# EVmulator_T85.net
KiCad netlist of a schematic drawn in EAGLE
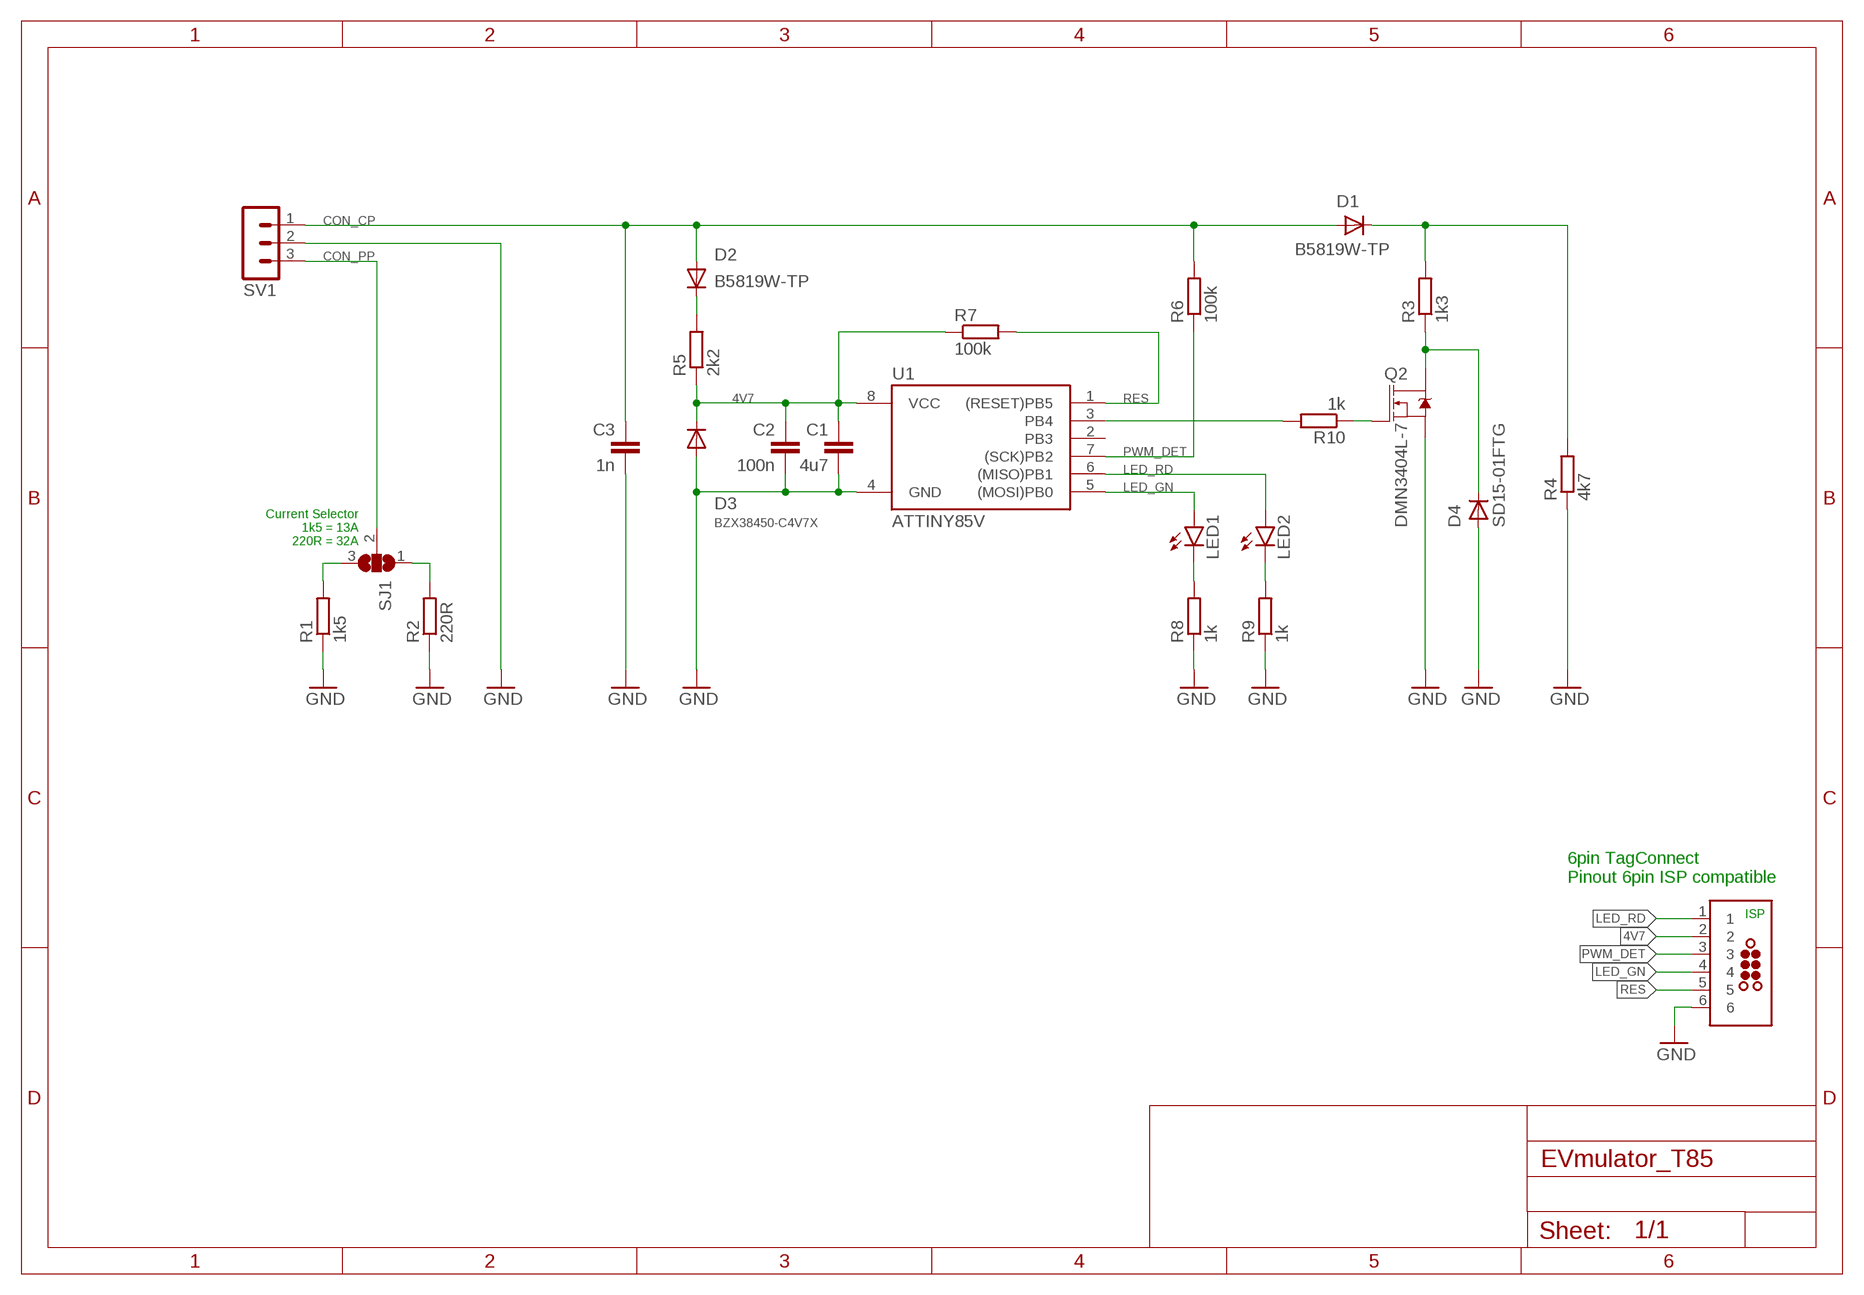
[diagram p0: schematic, sheet 1]

(export (version "E")
  (design (tool "Eeschema 10.0.6"))
  (components
    (comp (ref "C1")
      (value "4u7")
      (footprint "eagle-import:C0603")
      (libsource (lib "eagle-import") (part "C-EUC0603"))
    )
    (comp (ref "C2")
      (value "100n")
      (footprint "eagle-import:C0603")
      (libsource (lib "eagle-import") (part "C-EUC0603"))
    )
    (comp (ref "C3")
      (value "1n")
      (footprint "eagle-import:C0603")
      (libsource (lib "eagle-import") (part "C-EUC0603"))
    )
    (comp (ref "D1")
      (value "B5819W-TP")
      (footprint "eagle-import:SOD-123")
      (libsource (lib "eagle-import") (part "DIODESOD-123"))
    )
    (comp (ref "D2")
      (value "B5819W-TP")
      (footprint "eagle-import:SOD-123")
      (libsource (lib "eagle-import") (part "DIODESOD-123"))
    )
    (comp (ref "D3")
      (value "BZX38450-C4V7X")
      (footprint "eagle-import:SOD-323F")
      (libsource (lib "eagle-import") (part "DIODESOD-323F"))
    )
    (comp (ref "D4")
      (value "SD15-01FTG")
      (footprint "eagle-import:SOD-323F")
      (libsource (lib "eagle-import") (part "DIODESOD-323F"))
    )
    (comp (ref "J1")
      (value "TAG-CONNECT_TC2030-MCP-NL")
      (footprint "eagle-import:TAG-CONNECT_TC2030-MCP-NL")
      (libsource (lib "eagle-import") (part "TAG-CONNECT_TC2030-MCP-NL"))
    )
    (comp (ref "LED1")
      (value "LEDCHIP-LED0603")
      (footprint "eagle-import:CHIP-LED0603")
      (libsource (lib "eagle-import") (part "LEDCHIP-LED0603"))
    )
    (comp (ref "LED2")
      (value "LEDCHIP-LED0603")
      (footprint "eagle-import:CHIP-LED0603")
      (libsource (lib "eagle-import") (part "LEDCHIP-LED0603"))
    )
    (comp (ref "Q2")
      (value "DMN3404L-7")
      (footprint "eagle-import:SOT23-3")
      (libsource (lib "eagle-import") (part "MOSFET-NCH-AO3404A"))
    )
    (comp (ref "R1")
      (value "1k5")
      (footprint "eagle-import:R0805")
      (libsource (lib "eagle-import") (part "R-EU_R0805"))
    )
    (comp (ref "R2")
      (value "220R")
      (footprint "eagle-import:R0805")
      (libsource (lib "eagle-import") (part "R-EU_R0805"))
    )
    (comp (ref "R3")
      (value "1k3")
      (footprint "eagle-import:R0603")
      (libsource (lib "eagle-import") (part "R-EU_R0603"))
    )
    (comp (ref "R4")
      (value "4k7")
      (footprint "eagle-import:R0603")
      (libsource (lib "eagle-import") (part "R-EU_R0603"))
    )
    (comp (ref "R5")
      (value "2k2")
      (footprint "eagle-import:R0603")
      (libsource (lib "eagle-import") (part "R-EU_R0603"))
    )
    (comp (ref "R6")
      (value "100k")
      (footprint "eagle-import:R0603")
      (libsource (lib "eagle-import") (part "R-EU_R0603"))
    )
    (comp (ref "R7")
      (value "100k")
      (footprint "eagle-import:R0603")
      (libsource (lib "eagle-import") (part "R-EU_R0603"))
    )
    (comp (ref "R8")
      (value "1k")
      (footprint "eagle-import:R0603")
      (libsource (lib "eagle-import") (part "R-EU_R0603"))
    )
    (comp (ref "R9")
      (value "1k")
      (footprint "eagle-import:R0603")
      (libsource (lib "eagle-import") (part "R-EU_R0603"))
    )
    (comp (ref "R10")
      (value "1k")
      (footprint "eagle-import:R0603")
      (libsource (lib "eagle-import") (part "R-EU_R0603"))
    )
    (comp (ref "SJ1")
      (value "SJ2W")
      (footprint "eagle-import:SJ_2")
      (libsource (lib "eagle-import") (part "SJ2W"))
    )
    (comp (ref "SV1")
      (value "MA03-1")
      (footprint "eagle-import:MA03-1")
      (libsource (lib "eagle-import") (part "MA03-1"))
    )
    (comp (ref "U1")
      (value "ATTINY85V")
      (footprint "eagle-import:SOIC8")
      (libsource (lib "eagle-import") (part "ATTINY25/45/85-20SU"))
    )
  )
  (nets
    (net (code "1") (name "/CON_CP") (class "Default")
      (node (ref "C3") (pin "1") (pinfunction "1_1") (pintype "passive"))
      (node (ref "D1") (pin "A") (pinfunction "A_A") (pintype "passive"))
      (node (ref "D2") (pin "A") (pinfunction "A_A") (pintype "passive"))
      (node (ref "R6") (pin "2") (pinfunction "2_2") (pintype "passive"))
      (node (ref "SV1") (pin "1") (pinfunction "1_1") (pintype "passive"))
    )
    (net (code "2") (name "/CON_PP") (class "Default")
      (node (ref "SJ1") (pin "2") (pinfunction "2_2") (pintype "passive"))
      (node (ref "SV1") (pin "3") (pinfunction "3_3") (pintype "passive"))
    )
    (net (code "3") (name "4V7") (class "Default")
      (node (ref "C1") (pin "1") (pinfunction "1_1") (pintype "passive"))
      (node (ref "C2") (pin "1") (pinfunction "1_1") (pintype "passive"))
      (node (ref "D3") (pin "C") (pinfunction "C_C") (pintype "passive"))
      (node (ref "J1") (pin "2") (pinfunction "2_2") (pintype "power_in"))
      (node (ref "R5") (pin "1") (pinfunction "1_1") (pintype "passive"))
      (node (ref "R7") (pin "1") (pinfunction "1_1") (pintype "passive"))
      (node (ref "U1") (pin "8") (pinfunction "VCC_8") (pintype "power_in"))
    )
    (net (code "4") (name "GND") (class "Default")
      (node (ref "C1") (pin "2") (pinfunction "2_2") (pintype "passive"))
      (node (ref "C2") (pin "2") (pinfunction "2_2") (pintype "passive"))
      (node (ref "C3") (pin "2") (pinfunction "2_2") (pintype "passive"))
      (node (ref "D3") (pin "A") (pinfunction "A_A") (pintype "passive"))
      (node (ref "D4") (pin "A") (pinfunction "A_A") (pintype "passive"))
      (node (ref "J1") (pin "6") (pinfunction "6_6") (pintype "bidirectional"))
      (node (ref "Q2") (pin "2") (pinfunction "S_2") (pintype "bidirectional"))
      (node (ref "R1") (pin "1") (pinfunction "1_1") (pintype "passive"))
      (node (ref "R2") (pin "1") (pinfunction "1_1") (pintype "passive"))
      (node (ref "R4") (pin "1") (pinfunction "1_1") (pintype "passive"))
      (node (ref "R8") (pin "1") (pinfunction "1_1") (pintype "passive"))
      (node (ref "R9") (pin "1") (pinfunction "1_1") (pintype "passive"))
      (node (ref "SV1") (pin "2") (pinfunction "2_2") (pintype "passive"))
      (node (ref "U1") (pin "4") (pinfunction "GND_4") (pintype "power_in"))
    )
    (net (code "5") (name "LED_GN") (class "Default")
      (node (ref "J1") (pin "4") (pinfunction "4_4") (pintype "bidirectional"))
      (node (ref "LED1") (pin "A") (pinfunction "A_A") (pintype "passive"))
      (node (ref "U1") (pin "5") (pinfunction "(MOSI)PB0_5") (pintype "bidirectional"))
    )
    (net (code "6") (name "LED_RD") (class "Default")
      (node (ref "J1") (pin "1") (pinfunction "1_1") (pintype "passive"))
      (node (ref "LED2") (pin "A") (pinfunction "A_A") (pintype "passive"))
      (node (ref "U1") (pin "6") (pinfunction "(MISO)PB1_6") (pintype "bidirectional"))
    )
    (net (code "7") (name "Net-(D1-PadC)") (class "Default")
      (node (ref "D1") (pin "C") (pinfunction "C_C") (pintype "passive"))
      (node (ref "R3") (pin "2") (pinfunction "2_2") (pintype "passive"))
      (node (ref "R4") (pin "2") (pinfunction "2_2") (pintype "passive"))
    )
    (net (code "8") (name "Net-(D2-PadC)") (class "Default")
      (node (ref "D2") (pin "C") (pinfunction "C_C") (pintype "passive"))
      (node (ref "R5") (pin "2") (pinfunction "2_2") (pintype "passive"))
    )
    (net (code "9") (name "Net-(LED1-PadC)") (class "Default")
      (node (ref "LED1") (pin "C") (pinfunction "C_C") (pintype "passive"))
      (node (ref "R8") (pin "2") (pinfunction "2_2") (pintype "passive"))
    )
    (net (code "10") (name "Net-(LED2-PadC)") (class "Default")
      (node (ref "LED2") (pin "C") (pinfunction "C_C") (pintype "passive"))
      (node (ref "R9") (pin "2") (pinfunction "2_2") (pintype "passive"))
    )
    (net (code "11") (name "Net-(Q2-D)") (class "Default")
      (node (ref "D4") (pin "C") (pinfunction "C_C") (pintype "passive"))
      (node (ref "Q2") (pin "3") (pinfunction "D_3") (pintype "bidirectional"))
      (node (ref "R3") (pin "1") (pinfunction "1_1") (pintype "passive"))
    )
    (net (code "12") (name "Net-(Q2-G)") (class "Default")
      (node (ref "Q2") (pin "1") (pinfunction "G_1") (pintype "bidirectional"))
      (node (ref "R10") (pin "1") (pinfunction "1_1") (pintype "passive"))
    )
    (net (code "13") (name "Net-(R1-Pad2)") (class "Default")
      (node (ref "R1") (pin "2") (pinfunction "2_2") (pintype "passive"))
      (node (ref "SJ1") (pin "3") (pinfunction "3_3") (pintype "passive"))
    )
    (net (code "14") (name "Net-(R2-Pad2)") (class "Default")
      (node (ref "R2") (pin "2") (pinfunction "2_2") (pintype "passive"))
      (node (ref "SJ1") (pin "1") (pinfunction "1_1") (pintype "passive"))
    )
    (net (code "15") (name "Net-(U1-PB4)") (class "Default")
      (node (ref "R10") (pin "2") (pinfunction "2_2") (pintype "passive"))
      (node (ref "U1") (pin "3") (pinfunction "PB4_3") (pintype "bidirectional"))
    )
    (net (code "16") (name "PWM_DET") (class "Default")
      (node (ref "J1") (pin "3") (pinfunction "3_3") (pintype "power_in"))
      (node (ref "R6") (pin "1") (pinfunction "1_1") (pintype "passive"))
      (node (ref "U1") (pin "7") (pinfunction "(SCK)PB2_7") (pintype "bidirectional"))
    )
    (net (code "17") (name "RES") (class "Default")
      (node (ref "J1") (pin "5") (pinfunction "5_5") (pintype "output"))
      (node (ref "R7") (pin "2") (pinfunction "2_2") (pintype "passive"))
      (node (ref "U1") (pin "1") (pinfunction "(RESET)PB5_1") (pintype "bidirectional"))
    )
    (net (code "18") (name "unconnected-(U1-PB3-Pad2)") (class "Default")
      (node (ref "U1") (pin "2") (pinfunction "PB3_2") (pintype "bidirectional"))
    )
  )
)
